# power_path_control_switchable.net
KiCad netlist of a schematic drawn in Altium Designer
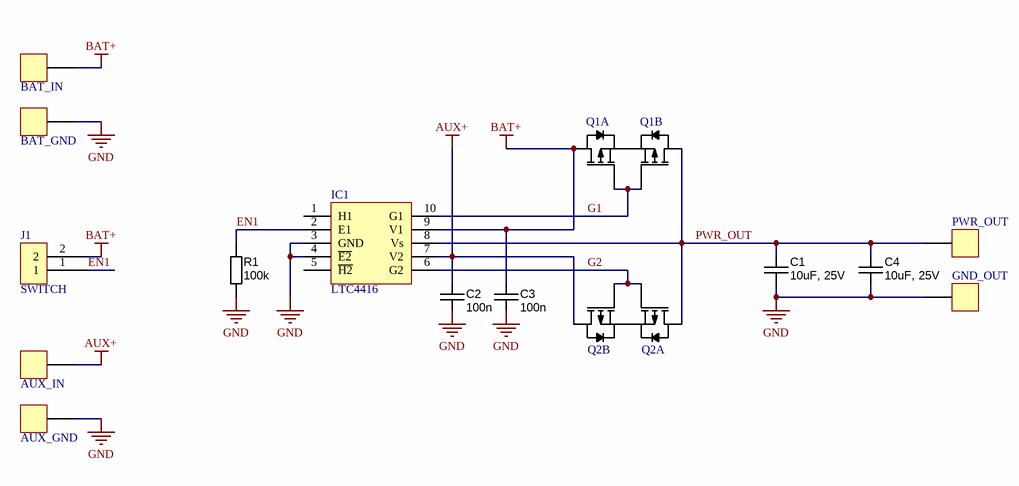
[diagram p0: power_path_control_switchable.SchDoc]

(export (version "E")
  (design (tool "Eeschema 10.0.6"))
  (components
    (comp (ref "AUX_GND")
      (value "HEADER-1")
      (footprint "POWER-PAD-4x3")
      (libsource (lib "connectors") (part "HEADER-1"))
    )
    (comp (ref "AUX_IN")
      (value "HEADER-1")
      (footprint "POWER-PAD-4x3")
      (libsource (lib "connectors") (part "HEADER-1"))
    )
    (comp (ref "BAT_GND")
      (value "HEADER-1")
      (footprint "POWER-PAD-4x3")
      (libsource (lib "connectors") (part "HEADER-1"))
    )
    (comp (ref "BAT_IN")
      (value "HEADER-1")
      (footprint "POWER-PAD-4x3")
      (libsource (lib "connectors") (part "HEADER-1"))
    )
    (comp (ref "C1")
      (value "10uF, 25V")
      (footprint "CAPC3216X180N")
      (description "Capacitor SMD Cer 6.8nF 5% 50V NP0 1206")
      (fields (field (name "TOLERANCE") "±5%"))
      (libsource (lib "PBL - Capacitors") (part "CAPC_6n8_1206_NP0_50V"))
    )
    (comp (ref "C2")
      (value "100n")
      (footprint "CAPC1608X90N")
      (description "Capacitor SMD Cer 10nF 10% 50V X7R 0603")
      (fields (field (name "TOLERANCE") "±10%"))
      (libsource (lib "PBL - Capacitors") (part "CAPC_10n_0603_X7R_50V_10%"))
    )
    (comp (ref "C3")
      (value "100n")
      (footprint "CAPC1608X90N")
      (description "Capacitor SMD Cer 10nF 10% 50V X7R 0603")
      (fields (field (name "TOLERANCE") "±10%"))
      (libsource (lib "PBL - Capacitors") (part "CAPC_10n_0603_X7R_50V_10%"))
    )
    (comp (ref "C4")
      (value "10uF, 25V")
      (footprint "CAPC3216X180N")
      (description "Capacitor SMD Cer 6.8nF 5% 50V NP0 1206")
      (fields (field (name "TOLERANCE") "±5%"))
      (libsource (lib "PBL - Capacitors") (part "CAPC_6n8_1206_NP0_50V"))
    )
    (comp (ref "GND_OUT")
      (value "HEADER-1")
      (footprint "POWER-PAD-4x3")
      (libsource (lib "") (part "HEADER-1_1"))
    )
    (comp (ref "IC1")
      (value "LTC4416")
      (footprint "MSOP-10")
      (description "PowerPath Controller, 3.6-36V, MSOP-10, LTC4416, Linear Technology")
      (fields
        (field (name "MANUFACTURER") "Analog Devices / Linear Technology")
        (field (name "MANUFACTURER PART NUMBER") "LTC4416EMS#PBF")
      )
      (libsource (lib "digital") (part "LTC4416"))
    )
    (comp (ref "J1")
      (value "SWITCH")
      (footprint "PADS-2-1020")
      (libsource (lib "connectors") (part "HEADER-2"))
    )
    (comp (ref "PWR_OUT")
      (value "HEADER-1")
      (footprint "POWER-PAD-4x3")
      (libsource (lib "") (part "HEADER-1_1"))
    )
    (comp (ref "Q1")
      (value "SI5997DU")
      (footprint "POWERPAK-CHIPFET-DUAL")
      (description "MOSFET, DUAL P-CHANNEL, 30Vin, 6A, 0.054R, SI5997DU-T1-GE3, PowerPAK ChipFET Dual")
      (fields
        (field (name "MANUFACTURER") "Vishay Siliconix")
        (field (name "MANUFACTURER PART NUMBER") "SI5997DU-T1-GE3")
      )
      (libsource (lib "mosfets") (part "SI5997DU"))
    )
    (comp (ref "Q2")
      (value "SI5997DU")
      (footprint "POWERPAK-CHIPFET-DUAL")
      (description "MOSFET, DUAL P-CHANNEL, 30Vin, 6A, 0.054R, SI5997DU-T1-GE3, PowerPAK ChipFET Dual")
      (fields
        (field (name "MANUFACTURER") "Vishay Siliconix")
        (field (name "MANUFACTURER PART NUMBER") "SI5997DU-T1-GE3")
      )
      (libsource (lib "mosfets") (part "SI5997DU"))
    )
    (comp (ref "R1")
      (value "100k")
      (footprint "RESC1608X55N")
      (description "Resistor SMD chip 100k Ohm 0.1W 1% 0603")
      (fields (field (name "TOLERANCE") "±1%") (field (name "Comment") "Thick Film"))
      (libsource (lib "PBL - Resistors") (part "RES_100K_0603_1%"))
    )
  )
  (nets
    (net (code "1") (name "/EN1") (class "Default")
      (node (ref "IC1") (pin "2") (pinfunction "E1_2") (pintype "passive"))
      (node (ref "J1") (pin "1") (pinfunction "1_1") (pintype "passive"))
      (node (ref "R1") (pin "1") (pinfunction "1_1") (pintype "passive"))
    )
    (net (code "2") (name "/G1") (class "Default")
      (node (ref "IC1") (pin "10") (pinfunction "G1_10") (pintype "passive"))
      (node (ref "Q1") (pin "G1") (pinfunction "G1_G1") (pintype "passive"))
      (node (ref "Q1") (pin "G2") (pinfunction "G2_G2") (pintype "passive"))
    )
    (net (code "3") (name "/G2") (class "Default")
      (node (ref "IC1") (pin "6") (pinfunction "G2_6") (pintype "passive"))
      (node (ref "Q2") (pin "G1") (pinfunction "G1_G1") (pintype "passive"))
      (node (ref "Q2") (pin "G2") (pinfunction "G2_G2") (pintype "passive"))
    )
    (net (code "4") (name "/PWR_OUT") (class "Default")
      (node (ref "C1") (pin "1") (pintype "passive"))
      (node (ref "C4") (pin "1") (pintype "passive"))
      (node (ref "IC1") (pin "8") (pinfunction "Vs_8") (pintype "passive"))
      (node (ref "PWR_OUT") (pin "1") (pinfunction "1_1") (pintype "passive"))
      (node (ref "Q1") (pin "D2") (pinfunction "D2_D2") (pintype "passive"))
      (node (ref "Q2") (pin "D1") (pinfunction "D1_D1") (pintype "passive"))
    )
    (net (code "5") (name "AUX+") (class "Default")
      (node (ref "AUX_IN") (pin "1") (pinfunction "1_1") (pintype "passive"))
      (node (ref "C2") (pin "1") (pintype "passive"))
      (node (ref "IC1") (pin "7") (pinfunction "V2_7") (pintype "passive"))
      (node (ref "Q2") (pin "D2") (pinfunction "D2_D2") (pintype "passive"))
    )
    (net (code "6") (name "BAT+") (class "Default")
      (node (ref "BAT_IN") (pin "1") (pinfunction "1_1") (pintype "passive"))
      (node (ref "C3") (pin "1") (pintype "passive"))
      (node (ref "IC1") (pin "9") (pinfunction "V1_9") (pintype "passive"))
      (node (ref "J1") (pin "2") (pinfunction "2_2") (pintype "passive"))
      (node (ref "Q1") (pin "D1") (pinfunction "D1_D1") (pintype "passive"))
    )
    (net (code "7") (name "GND") (class "Default")
      (node (ref "AUX_GND") (pin "1") (pinfunction "1_1") (pintype "passive"))
      (node (ref "BAT_GND") (pin "1") (pinfunction "1_1") (pintype "passive"))
      (node (ref "C1") (pin "2") (pintype "passive"))
      (node (ref "C2") (pin "2") (pintype "passive"))
      (node (ref "C3") (pin "2") (pintype "passive"))
      (node (ref "C4") (pin "2") (pintype "passive"))
      (node (ref "GND_OUT") (pin "1") (pinfunction "1_1") (pintype "passive"))
      (node (ref "IC1") (pin "3") (pinfunction "GND_3") (pintype "passive"))
      (node (ref "IC1") (pin "4") (pinfunction "~{E2}_4") (pintype "passive"))
      (node (ref "R1") (pin "2") (pinfunction "2_2") (pintype "passive"))
    )
    (net (code "8") (name "Net-(Q1-PadS1)") (class "Default")
      (node (ref "Q1") (pin "S1") (pinfunction "S1_S1") (pintype "passive"))
      (node (ref "Q1") (pin "S2") (pinfunction "S2_S2") (pintype "passive"))
    )
    (net (code "9") (name "Net-(Q2-PadS1)") (class "Default")
      (node (ref "Q2") (pin "S1") (pinfunction "S1_S1") (pintype "passive"))
      (node (ref "Q2") (pin "S2") (pinfunction "S2_S2") (pintype "passive"))
    )
    (net (code "10") (name "unconnected-(IC1-H1-Pad1)") (class "Default")
      (node (ref "IC1") (pin "1") (pinfunction "H1_1") (pintype "passive"))
    )
    (net (code "11") (name "unconnected-(IC1-~{H2}-Pad5)") (class "Default")
      (node (ref "IC1") (pin "5") (pinfunction "~{H2}_5") (pintype "passive"))
    )
  )
)
